# STM32F1_CNC_SCHA.net
KiCad netlist of a schematic drawn in Altium Designer
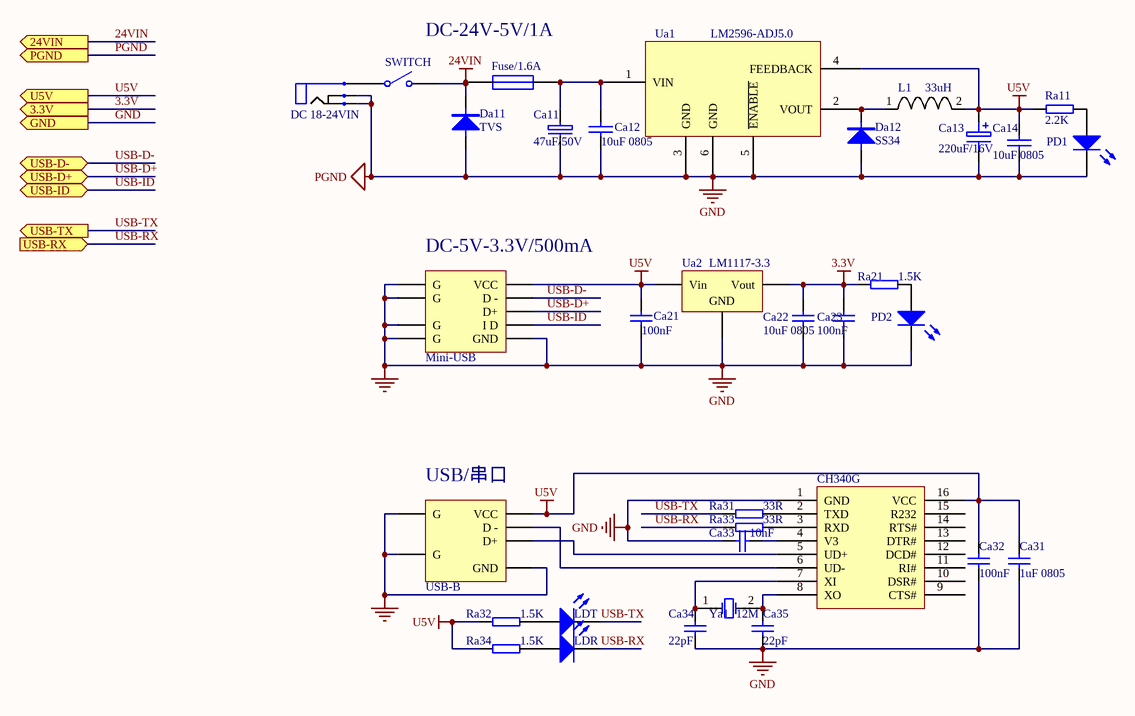
[diagram p0: STM32F1_CNC_SCHA.SchDoc]

(export (version "E")
  (design (tool "Eeschema 10.0.6"))
  (components
    (comp (ref "Ca11")
      (value "47uF/50V")
      (footprint "SMD-EC-F6.3")
      (description "Electro Capacitor")
      (libsource (lib "WEDOLIB") (part "EC1"))
    )
    (comp (ref "Ca12")
      (value "10uF 0805")
      (footprint "0805")
      (description "Capacitor")
      (libsource (lib "*") (part "CAP"))
    )
    (comp (ref "Ca13")
      (value "220uF/16V")
      (footprint "SMD-EC-F6.3")
      (description "ELECTR")
      (libsource (lib "*") (part "ELECTR"))
    )
    (comp (ref "Ca14")
      (value "10uF 0805")
      (footprint "0805")
      (description "Capacitor")
      (libsource (lib "*") (part "CAP"))
    )
    (comp (ref "Ca21")
      (value "100nF")
      (footprint "0805")
      (description "0603  X5R")
      (fields (field (name "TOLERANCE") "10%"))
      (libsource (lib "MB963_1") (part "CAP SMD 0603  X5R 1礔 25V 10%"))
    )
    (comp (ref "Ca22")
      (value "10uF 0805")
      (footprint "0805")
      (description "0603  X5R 1礔")
      (fields (field (name "TOLERANCE") "10%"))
      (libsource (lib "MB963_1") (part "CAP SMD 0603  X5R 1礔 25V 10%"))
    )
    (comp (ref "Ca23")
      (value "100nF")
      (footprint "0603")
      (description "Capacitor 0402 / 0603 / 0805")
      (libsource (lib "MCD_TOOLS") (part "Capacitor_ST"))
    )
    (comp (ref "Ca31")
      (value "1uF 0805")
      (footprint "0805")
      (description "Capacitor")
      (fields (field (name "PUBLISHER") "Altium Limited"))
      (libsource (lib "Miscellaneous Devices") (part "Cap"))
    )
    (comp (ref "Ca32")
      (value "100nF")
      (footprint "0603")
      (description "Capacitor")
      (fields (field (name "PUBLISHER") "Altium Limited"))
      (libsource (lib "Miscellaneous Devices") (part "Cap"))
    )
    (comp (ref "Ca33")
      (value "10nF")
      (footprint "0603")
      (description "Capacitor")
      (fields (field (name "PUBLISHER") "Altium Limited"))
      (libsource (lib "Miscellaneous Devices") (part "Cap"))
    )
    (comp (ref "Ca34")
      (value "22pF")
      (footprint "0603")
      (description "Capacitor")
      (fields (field (name "PUBLISHER") "Altium Limited"))
      (libsource (lib "Miscellaneous Devices") (part "Cap"))
    )
    (comp (ref "Ca35")
      (value "22pF")
      (footprint "0603")
      (description "Capacitor")
      (fields (field (name "PUBLISHER") "Altium Limited"))
      (libsource (lib "Miscellaneous Devices") (part "Cap"))
    )
    (comp (ref "CH340G") (value "CH340G") (footprint "SO-16") (libsource (lib "CH340G") (part "Component_1")))
    (comp (ref "Da11")
      (value "TVS")
      (footprint "SMA")
      (description "Low-Loss RF Switching Diode")
      (libsource (lib "*") (part "DIODE"))
    )
    (comp (ref "Da12")
      (value "SS34")
      (footprint "SMA")
      (description "D")
      (libsource (lib "*") (part "DIODE"))
    )
    (comp (ref "DC 18-24VIN")
      (value "DC")
      (footprint "DC-9V")
      (libsource (lib "STM32F1_CNC_Schlib") (part "DC-5.5mm"))
    )
    (comp (ref "Fuse/1.6A")
      (value "Fuse")
      (footprint "1812")
      (libsource (lib "STM32F1_CNC_Schlib") (part "Fuse"))
    )
    (comp (ref "L1") (value "33uH") (footprint "L") (description "L") (libsource (lib "*") (part "L")))
    (comp (ref "LDR")
      (value "LED")
      (footprint "LED-0805")
      (description "Typical RED, GREEN, YELLOW, AMBER GaAs LED")
      (fields (field (name "PUBLISHER") "Altium Limited"))
      (libsource (lib "Miscellaneous Devices") (part "LED2"))
    )
    (comp (ref "LDT")
      (value "LED")
      (footprint "LED-0805")
      (description "Typical RED, GREEN, YELLOW, AMBER GaAs LED")
      (fields (field (name "PUBLISHER") "Altium Limited"))
      (libsource (lib "Miscellaneous Devices") (part "LED2"))
    )
    (comp (ref "Mini-USB")
      (value "Mini-USB")
      (footprint "USB-mini-S")
      (libsource (lib "") (part "Mini-USB_G_1"))
    )
    (comp (ref "PD1")
      (value "LED")
      (footprint "LED-0805")
      (description "Typical RED, GREEN, YELLOW, AMBER GaAs LED")
      (fields (field (name "PUBLISHER") "Altium Limited"))
      (libsource (lib "Miscellaneous Devices") (part "LED2"))
    )
    (comp (ref "PD2")
      (value "LED")
      (footprint "LED-0805")
      (description "Typical RED, GREEN, YELLOW, AMBER GaAs LED")
      (fields (field (name "PUBLISHER") "Altium Limited"))
      (libsource (lib "Miscellaneous Devices") (part "LED2"))
    )
    (comp (ref "Ra11")
      (value "2.2K")
      (footprint "0805")
      (description "Resister")
      (libsource (lib "WEDOLIB") (part "RES1"))
    )
    (comp (ref "Ra21")
      (value "1.5K")
      (footprint "0603")
      (description "Resister")
      (libsource (lib "WEDOLIB") (part "RES1"))
    )
    (comp (ref "Ra31")
      (value "33R")
      (footprint "0603")
      (description "Resister")
      (libsource (lib "WEDOLIB") (part "RES1"))
    )
    (comp (ref "Ra32")
      (value "1.5K")
      (footprint "0603")
      (description "Resister")
      (libsource (lib "WEDOLIB") (part "RES1"))
    )
    (comp (ref "Ra33")
      (value "33R")
      (footprint "0603")
      (description "Resister")
      (libsource (lib "WEDOLIB") (part "RES1"))
    )
    (comp (ref "Ra34")
      (value "1.5K")
      (footprint "0603")
      (description "Resister")
      (libsource (lib "WEDOLIB") (part "RES1"))
    )
    (comp (ref "SWITCH")
      (value "SW-SPST")
      (footprint "SWTCH")
      (description "Single-Pole, Single-Throw Switch")
      (fields (field (name "PUBLISHER") "Altium Limited"))
      (libsource (lib "Miscellaneous Devices") (part "SW-SPST"))
    )
    (comp (ref "Ua1")
      (value "LM2596-ADJ5.0")
      (footprint "LM2596S")
      (description "LM2575")
      (libsource (lib "DJDSch") (part "LM2575"))
    )
    (comp (ref "Ua2")
      (value "LM1117-3.3")
      (footprint "SOT223")
      (description "Voltage Regulator")
      (fields (field (name "PUBLISHER") "Altium Limited"))
      (libsource (lib "Miscellaneous Devices") (part "Volt Reg"))
    )
    (comp (ref "USB-B")
      (value "USB-B")
      (footprint "USB-B2")
      (libsource (lib "STM32F1_CNC_Schlib") (part "Mini-USB_G"))
    )
    (comp (ref "Ya1")
      (value "12M")
      (footprint "XTAL-3215-2P")
      (description "Crystal Oscillator")
      (fields (field (name "PUBLISHER") "Altium Limited"))
      (libsource (lib "Miscellaneous Devices") (part "XTAL"))
    )
  )
  (nets
    (net (code "1") (name "/USB-D+") (class "Default")
      (node (ref "Mini-USB") (pin "3") (pinfunction "D+_3") (pintype "passive"))
    )
    (net (code "2") (name "/USB-D-") (class "Default")
      (node (ref "Mini-USB") (pin "2") (pinfunction "D_-_2") (pintype "passive"))
    )
    (net (code "3") (name "/USB-ID") (class "Default")
      (node (ref "Mini-USB") (pin "4") (pinfunction "I_D_4") (pintype "passive"))
    )
    (net (code "4") (name "/USB-RX") (class "Default")
      (node (ref "LDR") (pin "2") (pinfunction "K_2") (pintype "passive"))
      (node (ref "Ra33") (pin "2") (pinfunction "2_2") (pintype "passive"))
    )
    (net (code "5") (name "/USB-TX") (class "Default")
      (node (ref "LDT") (pin "2") (pinfunction "K_2") (pintype "passive"))
      (node (ref "Ra31") (pin "2") (pinfunction "2_2") (pintype "passive"))
    )
    (net (code "6") (name "3.3V") (class "Default")
      (node (ref "Ca22") (pin "1") (pinfunction "1_1") (pintype "passive"))
      (node (ref "Ca23") (pin "2") (pinfunction "2_2") (pintype "passive"))
      (node (ref "Ra21") (pin "2") (pinfunction "2_2") (pintype "passive"))
      (node (ref "Ua2") (pin "2") (pinfunction "Vout_2") (pintype "passive"))
    )
    (net (code "7") (name "24VIN") (class "Default")
      (node (ref "Da11") (pin "2") (pinfunction "2_2") (pintype "passive"))
      (node (ref "Fuse/1.6A") (pin "1") (pinfunction "1_1") (pintype "passive"))
      (node (ref "SWITCH") (pin "1") (pinfunction "NO_1") (pintype "passive"))
    )
    (net (code "8") (name "<NO NET>") (class "Default")
      (node (ref "CH340G") (pin "1") (pinfunction "GND_1") (pintype "passive"))
      (node (ref "Ca11") (pin "2") (pintype "passive"))
      (node (ref "Ca12") (pin "2") (pinfunction "2_2") (pintype "passive"))
      (node (ref "Ca13") (pin "2") (pinfunction "2_2") (pintype "passive"))
      (node (ref "Ca14") (pin "2") (pinfunction "2_2") (pintype "passive"))
      (node (ref "Ca21") (pin "1") (pinfunction "1_1") (pintype "passive"))
      (node (ref "Ca22") (pin "2") (pinfunction "2_2") (pintype "passive"))
      (node (ref "Ca23") (pin "1") (pinfunction "1_1") (pintype "passive"))
      (node (ref "Ca31") (pin "2") (pinfunction "2_2") (pintype "passive"))
      (node (ref "Ca32") (pin "2") (pinfunction "2_2") (pintype "passive"))
      (node (ref "Ca33") (pin "2") (pinfunction "2_2") (pintype "passive"))
      (node (ref "Ca34") (pin "1") (pinfunction "1_1") (pintype "passive"))
      (node (ref "Ca35") (pin "1") (pinfunction "1_1") (pintype "passive"))
      (node (ref "DC 18-24VIN") (pin "2") (pinfunction "2_2") (pintype "open_collector"))
      (node (ref "DC 18-24VIN") (pin "3") (pinfunction "3_3") (pintype "open_collector"))
      (node (ref "Da11") (pin "1") (pinfunction "1_1") (pintype "passive"))
      (node (ref "Da12") (pin "1") (pinfunction "1_1") (pintype "passive"))
      (node (ref "Mini-USB") (pin "0") (pinfunction "G_0") (pintype "passive"))
      (node (ref "Mini-USB") (pin "5") (pinfunction "GND_5") (pintype "passive"))
      (node (ref "PD1") (pin "2") (pinfunction "K_2") (pintype "passive"))
      (node (ref "PD2") (pin "2") (pinfunction "K_2") (pintype "passive"))
      (node (ref "USB-B") (pin "0") (pinfunction "G_0") (pintype "passive"))
      (node (ref "USB-B") (pin "4") (pinfunction "GND_4") (pintype "passive"))
      (node (ref "Ua1") (pin "3") (pinfunction "GND_3") (pintype "passive"))
      (node (ref "Ua1") (pin "5") (pinfunction "~{ENABLE}_5") (pintype "passive"))
      (node (ref "Ua1") (pin "6") (pinfunction "GND_6") (pintype "passive"))
      (node (ref "Ua2") (pin "1") (pinfunction "GND_1") (pintype "passive"))
    )
    (net (code "9") (name "Net-(CH340G-RXD)") (class "Default")
      (node (ref "CH340G") (pin "3") (pinfunction "RXD_3") (pintype "passive"))
      (node (ref "Ra33") (pin "1") (pinfunction "1_1") (pintype "passive"))
    )
    (net (code "10") (name "Net-(CH340G-TXD)") (class "Default")
      (node (ref "CH340G") (pin "2") (pinfunction "TXD_2") (pintype "passive"))
      (node (ref "Ra31") (pin "1") (pinfunction "1_1") (pintype "passive"))
    )
    (net (code "11") (name "Net-(CH340G-UD+)") (class "Default")
      (node (ref "CH340G") (pin "5") (pinfunction "UD+_5") (pintype "passive"))
      (node (ref "USB-B") (pin "3") (pinfunction "D+_3") (pintype "passive"))
    )
    (net (code "12") (name "Net-(CH340G-UD-)") (class "Default")
      (node (ref "CH340G") (pin "6") (pinfunction "UD-_6") (pintype "passive"))
      (node (ref "USB-B") (pin "2") (pinfunction "D_-_2") (pintype "passive"))
    )
    (net (code "13") (name "Net-(CH340G-V3)") (class "Default")
      (node (ref "CH340G") (pin "4") (pinfunction "V3_4") (pintype "passive"))
      (node (ref "Ca33") (pin "1") (pinfunction "1_1") (pintype "passive"))
    )
    (net (code "14") (name "Net-(CH340G-XI)") (class "Default")
      (node (ref "CH340G") (pin "7") (pinfunction "XI_7") (pintype "passive"))
      (node (ref "Ca34") (pin "2") (pinfunction "2_2") (pintype "passive"))
      (node (ref "Ya1") (pin "1") (pinfunction "OSC1_1") (pintype "passive"))
    )
    (net (code "15") (name "Net-(CH340G-XO)") (class "Default")
      (node (ref "CH340G") (pin "8") (pinfunction "XO_8") (pintype "passive"))
      (node (ref "Ca35") (pin "2") (pinfunction "2_2") (pintype "passive"))
      (node (ref "Ya1") (pin "2") (pinfunction "OSC2_2") (pintype "passive"))
    )
    (net (code "16") (name "Net-(LDR-A)") (class "Default")
      (node (ref "LDR") (pin "1") (pinfunction "A_1") (pintype "passive"))
      (node (ref "Ra34") (pin "1") (pinfunction "1_1") (pintype "passive"))
    )
    (net (code "17") (name "Net-(LDT-A)") (class "Default")
      (node (ref "LDT") (pin "1") (pinfunction "A_1") (pintype "passive"))
      (node (ref "Ra32") (pin "1") (pinfunction "1_1") (pintype "passive"))
    )
    (net (code "18") (name "Net-(PD1-A)") (class "Default")
      (node (ref "PD1") (pin "1") (pinfunction "A_1") (pintype "passive"))
      (node (ref "Ra11") (pin "1") (pinfunction "1_1") (pintype "passive"))
    )
    (net (code "19") (name "Net-(PD2-A)") (class "Default")
      (node (ref "PD2") (pin "1") (pinfunction "A_1") (pintype "passive"))
      (node (ref "Ra21") (pin "1") (pinfunction "1_1") (pintype "passive"))
    )
    (net (code "20") (name "Net-(SWITCH-COMMON)") (class "Default")
      (node (ref "DC 18-24VIN") (pin "1") (pinfunction "1_1") (pintype "open_collector"))
      (node (ref "SWITCH") (pin "2") (pinfunction "COMMON_2") (pintype "passive"))
    )
    (net (code "21") (name "Net-(Ua1-VIN)") (class "Default")
      (node (ref "Ca11") (pin "1") (pintype "passive"))
      (node (ref "Ca12") (pin "1") (pinfunction "1_1") (pintype "passive"))
      (node (ref "Fuse/1.6A") (pin "2") (pinfunction "2_2") (pintype "passive"))
      (node (ref "Ua1") (pin "1") (pinfunction "VIN_1") (pintype "passive"))
    )
    (net (code "22") (name "Net-(Ua1-VOUT)") (class "Default")
      (node (ref "Da12") (pin "2") (pinfunction "2_2") (pintype "passive"))
      (node (ref "L1") (pin "1") (pintype "passive"))
      (node (ref "Ua1") (pin "2") (pinfunction "VOUT_2") (pintype "passive"))
    )
    (net (code "23") (name "U5V") (class "Default")
      (node (ref "CH340G") (pin "16") (pinfunction "VCC_16") (pintype "passive"))
      (node (ref "Ca13") (pin "1") (pinfunction "1_1") (pintype "passive"))
      (node (ref "Ca14") (pin "1") (pinfunction "1_1") (pintype "passive"))
      (node (ref "Ca21") (pin "2") (pinfunction "2_2") (pintype "passive"))
      (node (ref "Ca31") (pin "1") (pinfunction "1_1") (pintype "passive"))
      (node (ref "Ca32") (pin "1") (pinfunction "1_1") (pintype "passive"))
      (node (ref "L1") (pin "2") (pintype "passive"))
      (node (ref "Mini-USB") (pin "1") (pinfunction "VCC_1") (pintype "passive"))
      (node (ref "Ra11") (pin "2") (pinfunction "2_2") (pintype "passive"))
      (node (ref "Ra32") (pin "2") (pinfunction "2_2") (pintype "passive"))
      (node (ref "Ra34") (pin "2") (pinfunction "2_2") (pintype "passive"))
      (node (ref "USB-B") (pin "1") (pinfunction "VCC_1") (pintype "passive"))
      (node (ref "Ua1") (pin "4") (pinfunction "FEEDBACK_4") (pintype "passive"))
      (node (ref "Ua2") (pin "3") (pinfunction "Vin_3") (pintype "passive"))
    )
    (net (code "24") (name "unconnected-(CH340G-CTS#-Pad9)") (class "Default")
      (node (ref "CH340G") (pin "9") (pinfunction "CTS#_9") (pintype "passive"))
    )
    (net (code "25") (name "unconnected-(CH340G-DCD#-Pad12)") (class "Default")
      (node (ref "CH340G") (pin "12") (pinfunction "DCD#_12") (pintype "passive"))
    )
    (net (code "26") (name "unconnected-(CH340G-DSR#-Pad10)") (class "Default")
      (node (ref "CH340G") (pin "10") (pinfunction "DSR#_10") (pintype "passive"))
    )
    (net (code "27") (name "unconnected-(CH340G-DTR#-Pad13)") (class "Default")
      (node (ref "CH340G") (pin "13") (pinfunction "DTR#_13") (pintype "passive"))
    )
    (net (code "28") (name "unconnected-(CH340G-R232-Pad15)") (class "Default")
      (node (ref "CH340G") (pin "15") (pinfunction "R232_15") (pintype "passive"))
    )
    (net (code "29") (name "unconnected-(CH340G-RI#-Pad11)") (class "Default")
      (node (ref "CH340G") (pin "11") (pinfunction "RI#_11") (pintype "passive"))
    )
    (net (code "30") (name "unconnected-(CH340G-RTS#-Pad14)") (class "Default")
      (node (ref "CH340G") (pin "14") (pinfunction "RTS#_14") (pintype "passive"))
    )
  )
)
